# Switch.net
KiCad netlist of a schematic drawn in Altium Designer
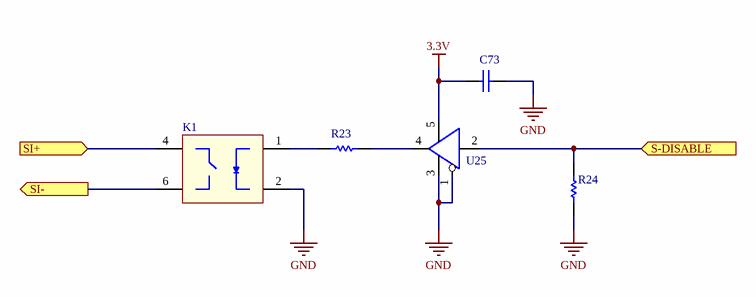
[diagram p0: Switch.SchDoc]

(export (version "E")
  (design (tool "Eeschema 10.0.6"))
  (components
    (comp (ref "C73")
      (value "C0603C104K5RACAUTO")
      (footprint "CAP-0603")
      (description "CAP CER 0.1uF 50V X7R 0603")
      (fields (field (name "MANUFACTURER") "Kemet") (field (name "TOLERANCE") "10%"))
      (libsource (lib "Kemet") (part "C0603C104K5RACAUTO"))
    )
    (comp (ref "K1")
      (value "~")
      (footprint "SMD6")
      (description "SSR RELAY SPST-NC 500MA 0-60V")
      (fields (field (name "MANUFACTURER") "Ixys"))
      (libsource (lib "Ixys") (part "LCB716S"))
    )
    (comp (ref "R23")
      (value "RC0603FR-07453RL")
      (footprint "RES-0603")
      (description "RES SMD 453 OHM 1% 1/10W 0603")
      (fields (field (name "TOLERANCE") "1%") (field (name "MANUFACTURER") "Yageo"))
      (libsource (lib "Yageo") (part "RC0603FR-07453RL"))
    )
    (comp (ref "R24")
      (value "RC0603FR-07100KL")
      (footprint "RES-0603")
      (description "RES SMD 100K OHM 1% 1/10W 0603")
      (fields (field (name "TOLERANCE") "1%") (field (name "MANUFACTURER") "Yageo"))
      (libsource (lib "Yageo") (part "RC0603FR-07100KL"))
    )
    (comp (ref "U25")
      (value "~")
      (footprint "SOT23-5")
      (description "IC BUFF TRI-ST UHS N-INV SOT23-5")
      (fields (field (name "MANUFACTURER") "Fairchild Semiconductor"))
      (libsource (lib "Fairchild") (part "NC7SZ125M5X"))
    )
  )
  (nets
    (net (code "1") (name "/S-DISABLE") (class "Default")
      (node (ref "R24") (pin "2") (pinfunction "2_2") (pintype "passive"))
      (node (ref "U25") (pin "2") (pinfunction "A_2") (pintype "passive"))
    )
    (net (code "2") (name "/SI+") (class "Default")
      (node (ref "K1") (pin "4") (pinfunction "4_4") (pintype "passive"))
    )
    (net (code "3") (name "/SI-") (class "Default")
      (node (ref "K1") (pin "6") (pinfunction "6_6") (pintype "passive"))
    )
    (net (code "4") (name "3.3V") (class "Default")
      (node (ref "C73") (pin "1") (pinfunction "1_1") (pintype "passive"))
      (node (ref "U25") (pin "5") (pinfunction "VCC_5") (pintype "passive"))
    )
    (net (code "5") (name "GND") (class "Default")
      (node (ref "C73") (pin "2") (pinfunction "2_2") (pintype "passive"))
      (node (ref "K1") (pin "2") (pinfunction "2_2") (pintype "passive"))
      (node (ref "R24") (pin "1") (pinfunction "1_1") (pintype "passive"))
      (node (ref "U25") (pin "1") (pinfunction "OE_1") (pintype "passive"))
      (node (ref "U25") (pin "3") (pinfunction "GND_3") (pintype "passive"))
    )
    (net (code "6") (name "Net-(K1-Pad1)") (class "Default")
      (node (ref "K1") (pin "1") (pinfunction "1_1") (pintype "passive"))
      (node (ref "R23") (pin "1") (pinfunction "1_1") (pintype "passive"))
    )
    (net (code "7") (name "Net-(U25-Y)") (class "Default")
      (node (ref "R23") (pin "2") (pinfunction "2_2") (pintype "passive"))
      (node (ref "U25") (pin "4") (pinfunction "Y_4") (pintype "passive"))
    )
  )
)
